# COM.net
KiCad netlist of a schematic drawn in Altium Designer
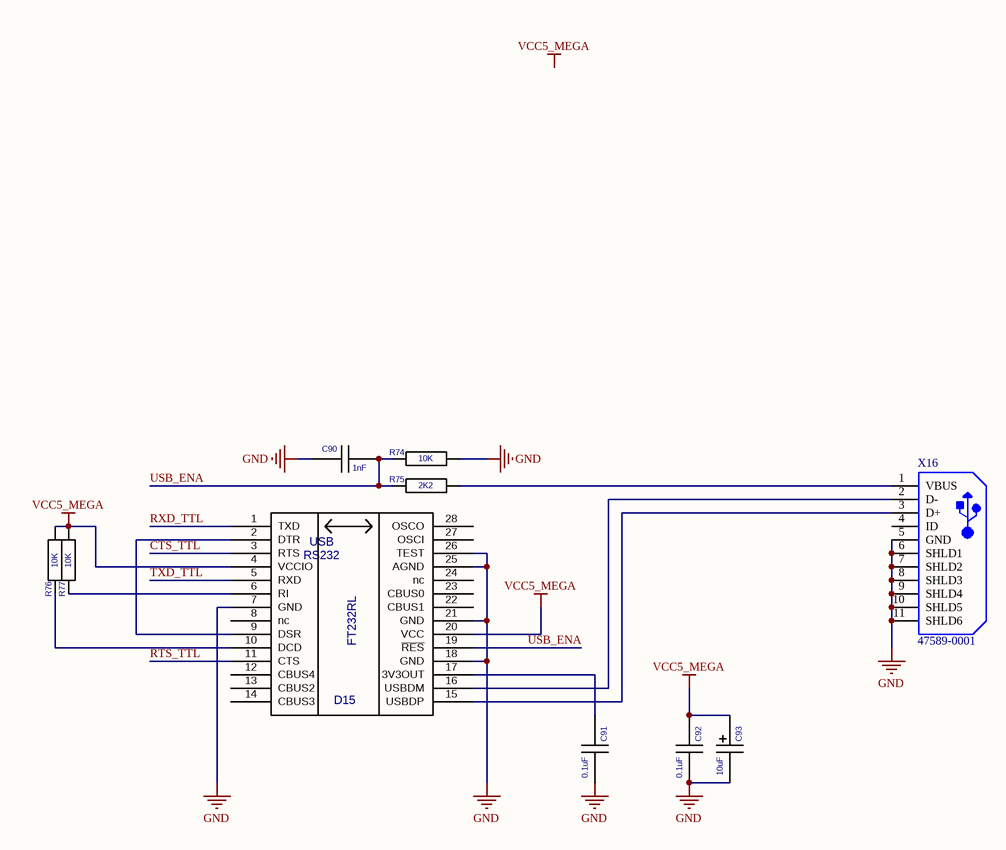
[diagram p0: COM.SchDoc]

(export (version "E")
  (design (tool "Eeschema 10.0.6"))
  (components
    (comp (ref "C90")
      (value "1nF")
      (footprint "C-CHIP")
      (description "CAPCHIP")
      (libsource (lib "*") (part "CAPCHIP"))
    )
    (comp (ref "C91")
      (value "0.1uF")
      (footprint "C-CHIP")
      (description "CAPCHIP")
      (libsource (lib "*") (part "CAPCHIP"))
    )
    (comp (ref "C92")
      (value "0.1uF")
      (footprint "C-CHIP")
      (description "CAPCHIP")
      (libsource (lib "*") (part "CAPCHIP"))
    )
    (comp (ref "C93")
      (value "10uF")
      (footprint "EC-CHIP")
      (description "ECAPCHIP")
      (libsource (lib "*") (part "ECAPCHIP"))
    )
    (comp (ref "D15") (value "FT232RL") (footprint "SSOP28") (libsource (lib "*") (part "FT232RL")))
    (comp (ref "R74")
      (value "10K")
      (footprint "R-CHIP")
      (description "RESCHIP")
      (libsource (lib "*") (part "RESCHIP"))
    )
    (comp (ref "R75")
      (value "2K2")
      (footprint "R-CHIP")
      (description "RESCHIP")
      (libsource (lib "*") (part "RESCHIP"))
    )
    (comp (ref "R76")
      (value "10K")
      (footprint "R-CHIP")
      (description "RESCHIP")
      (libsource (lib "*") (part "RESCHIP"))
    )
    (comp (ref "R77")
      (value "10K")
      (footprint "R-CHIP")
      (description "RESCHIP")
      (libsource (lib "*") (part "RESCHIP"))
    )
    (comp (ref "X16")
      (value "47589-0001")
      (footprint "MOLX-47589-0001_V")
      (description "Right Angle Female Type AB Micro USB Connector, 30 V, 1.8 A, -30 to 85 degC, RoHS, Tape and Reel")
      (fields (field (name "MANUFACTURER") "Molex"))
      (libsource (lib "Altium Content Vault") (part "USB-5-6SHLD"))
    )
  )
  (nets
    (net (code "1") (name "/CTS_TTL") (class "Default")
      (node (ref "D15") (pin "3") (pinfunction "RTS_3") (pintype "passive"))
    )
    (net (code "2") (name "/RTS_TTL") (class "Default")
      (node (ref "D15") (pin "11") (pinfunction "CTS_11") (pintype "passive"))
    )
    (net (code "3") (name "/RXD_TTL") (class "Default")
      (node (ref "D15") (pin "1") (pinfunction "TXD_1") (pintype "passive"))
    )
    (net (code "4") (name "/TXD_TTL") (class "Default")
      (node (ref "D15") (pin "5") (pinfunction "RXD_5") (pintype "passive"))
    )
    (net (code "5") (name "/USB_ENA") (class "Default")
      (node (ref "C90") (pin "2") (pinfunction "2_2") (pintype "passive"))
      (node (ref "D15") (pin "19") (pinfunction "~{RES}_19") (pintype "passive"))
      (node (ref "R74") (pin "2") (pinfunction "i/o1_2") (pintype "passive"))
      (node (ref "R75") (pin "2") (pinfunction "i/o1_2") (pintype "passive"))
    )
    (net (code "6") (name "GND") (class "Default")
      (node (ref "C90") (pin "1") (pinfunction "1_1") (pintype "passive"))
      (node (ref "C91") (pin "2") (pinfunction "2_2") (pintype "passive"))
      (node (ref "C92") (pin "2") (pinfunction "2_2") (pintype "passive"))
      (node (ref "C93") (pin "2") (pintype "passive"))
      (node (ref "D15") (pin "18") (pinfunction "GND_18") (pintype "passive"))
      (node (ref "D15") (pin "21") (pinfunction "GND_21") (pintype "passive"))
      (node (ref "D15") (pin "25") (pinfunction "AGND_25") (pintype "passive"))
      (node (ref "D15") (pin "26") (pinfunction "TEST_26") (pintype "passive"))
      (node (ref "D15") (pin "7") (pinfunction "GND_7") (pintype "passive"))
      (node (ref "R74") (pin "1") (pinfunction "i/o_1") (pintype "passive"))
      (node (ref "X16") (pin "10") (pinfunction "SHLD5_10") (pintype "passive"))
      (node (ref "X16") (pin "11") (pinfunction "SHLD6_11") (pintype "passive"))
      (node (ref "X16") (pin "5") (pinfunction "GND_5") (pintype "passive"))
      (node (ref "X16") (pin "6") (pinfunction "SHLD1_6") (pintype "passive"))
      (node (ref "X16") (pin "7") (pinfunction "SHLD2_7") (pintype "passive"))
      (node (ref "X16") (pin "8") (pinfunction "SHLD3_8") (pintype "passive"))
      (node (ref "X16") (pin "9") (pinfunction "SHLD4_9") (pintype "passive"))
    )
    (net (code "7") (name "Net-(D15-3V3OUT)") (class "Default")
      (node (ref "C91") (pin "1") (pinfunction "1_1") (pintype "passive"))
      (node (ref "D15") (pin "17") (pinfunction "3V3OUT_17") (pintype "passive"))
    )
    (net (code "8") (name "Net-(D15-DCD)") (class "Default")
      (node (ref "D15") (pin "10") (pinfunction "DCD_10") (pintype "passive"))
      (node (ref "R76") (pin "2") (pinfunction "i/o1_2") (pintype "passive"))
    )
    (net (code "9") (name "Net-(D15-DSR)") (class "Default")
      (node (ref "D15") (pin "2") (pinfunction "DTR_2") (pintype "passive"))
      (node (ref "D15") (pin "9") (pinfunction "DSR_9") (pintype "passive"))
    )
    (net (code "10") (name "Net-(D15-RI)") (class "Default")
      (node (ref "D15") (pin "6") (pinfunction "RI_6") (pintype "passive"))
      (node (ref "R77") (pin "2") (pinfunction "i/o1_2") (pintype "passive"))
    )
    (net (code "11") (name "Net-(D15-USBDM)") (class "Default")
      (node (ref "D15") (pin "16") (pinfunction "USBDM_16") (pintype "passive"))
      (node (ref "X16") (pin "2") (pinfunction "D-_2") (pintype "passive"))
    )
    (net (code "12") (name "Net-(D15-USBDP)") (class "Default")
      (node (ref "D15") (pin "15") (pinfunction "USBDP_15") (pintype "passive"))
      (node (ref "X16") (pin "3") (pinfunction "D+_3") (pintype "passive"))
    )
    (net (code "13") (name "Net-(R75-i{slash}o)") (class "Default")
      (node (ref "R75") (pin "1") (pinfunction "i/o_1") (pintype "passive"))
      (node (ref "X16") (pin "1") (pinfunction "VBUS_1") (pintype "passive"))
    )
    (net (code "14") (name "VCC5_MEGA") (class "Default")
      (node (ref "C92") (pin "1") (pinfunction "1_1") (pintype "passive"))
      (node (ref "C93") (pin "1") (pintype "passive"))
      (node (ref "D15") (pin "20") (pinfunction "VCC_20") (pintype "passive"))
      (node (ref "D15") (pin "4") (pinfunction "VCCIO_4") (pintype "passive"))
      (node (ref "R76") (pin "1") (pinfunction "i/o_1") (pintype "passive"))
      (node (ref "R77") (pin "1") (pinfunction "i/o_1") (pintype "passive"))
    )
    (net (code "15") (name "unconnected-(D15-CBUS0-Pad23)") (class "Default")
      (node (ref "D15") (pin "23") (pinfunction "CBUS0_23") (pintype "passive"))
    )
    (net (code "16") (name "unconnected-(D15-CBUS1-Pad22)") (class "Default")
      (node (ref "D15") (pin "22") (pinfunction "CBUS1_22") (pintype "passive"))
    )
    (net (code "17") (name "unconnected-(D15-CBUS2-Pad13)") (class "Default")
      (node (ref "D15") (pin "13") (pinfunction "CBUS2_13") (pintype "passive"))
    )
    (net (code "18") (name "unconnected-(D15-CBUS3-Pad14)") (class "Default")
      (node (ref "D15") (pin "14") (pinfunction "CBUS3_14") (pintype "passive"))
    )
    (net (code "19") (name "unconnected-(D15-CBUS4-Pad12)") (class "Default")
      (node (ref "D15") (pin "12") (pinfunction "CBUS4_12") (pintype "passive"))
    )
    (net (code "20") (name "unconnected-(D15-OSCI-Pad27)") (class "Default")
      (node (ref "D15") (pin "27") (pinfunction "OSCI_27") (pintype "passive"))
    )
    (net (code "21") (name "unconnected-(D15-OSCO-Pad28)") (class "Default")
      (node (ref "D15") (pin "28") (pinfunction "OSCO_28") (pintype "passive"))
    )
    (net (code "22") (name "unconnected-(D15-nc-Pad8)") (class "Default")
      (node (ref "D15") (pin "8") (pinfunction "nc_8") (pintype "passive"))
    )
    (net (code "23") (name "unconnected-(D15-nc-Pad24)") (class "Default")
      (node (ref "D15") (pin "24") (pinfunction "nc_24") (pintype "passive"))
    )
    (net (code "24") (name "unconnected-(X16-ID-Pad4)") (class "Default")
      (node (ref "X16") (pin "4") (pinfunction "ID_4") (pintype "passive"))
    )
  )
)
